# Punto1.net
KiCad netlist of a schematic drawn in Altium Designer
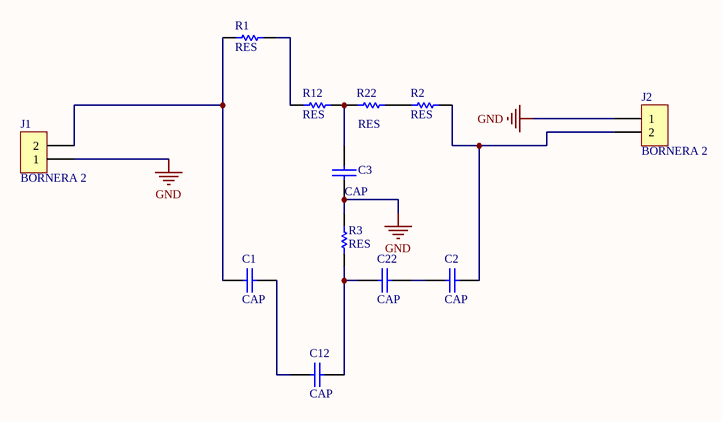
[diagram p0: Punto1.SchDoc]

(export (version "E")
  (design (tool "Eeschema 10.0.6"))
  (components
    (comp (ref "C1") (value "CAP") (footprint "CAP100") (libsource (lib "LIBEBAL") (part "CAP")))
    (comp (ref "C2") (value "CAP") (footprint "CAP100") (libsource (lib "LIBEBAL") (part "CAP")))
    (comp (ref "C3") (value "CAP") (footprint "CAP100") (libsource (lib "LIBEBAL") (part "CAP")))
    (comp (ref "C12") (value "CAP") (footprint "CAP100") (libsource (lib "LIBEBAL") (part "CAP")))
    (comp (ref "C22") (value "CAP") (footprint "CAP100") (libsource (lib "LIBEBAL") (part "CAP")))
    (comp (ref "J1") (value "BORNERA 2") (footprint "BORNERA2") (libsource (lib "") (part "BORNERA 2_1")))
    (comp (ref "J2")
      (value "BORNERA 2")
      (footprint "BORNERA2")
      (libsource (lib "LIBEBAL") (part "BORNERA 2"))
    )
    (comp (ref "R1") (value "RES") (footprint "RES400") (libsource (lib "LIBEBAL") (part "RES")))
    (comp (ref "R2") (value "RES") (footprint "RES400") (libsource (lib "LIBEBAL") (part "RES")))
    (comp (ref "R3") (value "RES") (footprint "RES400") (libsource (lib "LIBEBAL") (part "RES")))
    (comp (ref "R12") (value "RES") (footprint "RES400") (libsource (lib "LIBEBAL") (part "RES")))
    (comp (ref "R22") (value "RES") (footprint "RES400") (libsource (lib "LIBEBAL") (part "RES")))
  )
  (nets
    (net (code "1") (name "GND") (class "Default")
      (node (ref "C3") (pin "1") (pinfunction "1_1") (pintype "passive"))
      (node (ref "J1") (pin "1") (pinfunction "1_1") (pintype "passive"))
      (node (ref "J2") (pin "1") (pinfunction "1_1") (pintype "passive"))
      (node (ref "R3") (pin "2") (pinfunction "2_2") (pintype "passive"))
    )
    (net (code "2") (name "Net-(C1-Pad1)") (class "Default")
      (node (ref "C1") (pin "1") (pinfunction "1_1") (pintype "passive"))
      (node (ref "J1") (pin "2") (pinfunction "2_2") (pintype "passive"))
      (node (ref "R1") (pin "1") (pinfunction "1_1") (pintype "passive"))
    )
    (net (code "3") (name "Net-(C1-Pad2)") (class "Default")
      (node (ref "C1") (pin "2") (pinfunction "2_2") (pintype "passive"))
      (node (ref "C12") (pin "1") (pinfunction "1_1") (pintype "passive"))
    )
    (net (code "4") (name "Net-(C2-Pad1)") (class "Default")
      (node (ref "C2") (pin "1") (pinfunction "1_1") (pintype "passive"))
      (node (ref "C22") (pin "2") (pinfunction "2_2") (pintype "passive"))
    )
    (net (code "5") (name "Net-(C2-Pad2)") (class "Default")
      (node (ref "C2") (pin "2") (pinfunction "2_2") (pintype "passive"))
      (node (ref "J2") (pin "2") (pinfunction "2_2") (pintype "passive"))
      (node (ref "R2") (pin "2") (pinfunction "2_2") (pintype "passive"))
    )
    (net (code "6") (name "Net-(C3-Pad2)") (class "Default")
      (node (ref "C3") (pin "2") (pinfunction "2_2") (pintype "passive"))
      (node (ref "R12") (pin "2") (pinfunction "2_2") (pintype "passive"))
      (node (ref "R22") (pin "1") (pinfunction "1_1") (pintype "passive"))
    )
    (net (code "7") (name "Net-(C12-Pad2)") (class "Default")
      (node (ref "C12") (pin "2") (pinfunction "2_2") (pintype "passive"))
      (node (ref "C22") (pin "1") (pinfunction "1_1") (pintype "passive"))
      (node (ref "R3") (pin "1") (pinfunction "1_1") (pintype "passive"))
    )
    (net (code "8") (name "Net-(R1-Pad2)") (class "Default")
      (node (ref "R1") (pin "2") (pinfunction "2_2") (pintype "passive"))
      (node (ref "R12") (pin "1") (pinfunction "1_1") (pintype "passive"))
    )
    (net (code "9") (name "Net-(R2-Pad1)") (class "Default")
      (node (ref "R2") (pin "1") (pinfunction "1_1") (pintype "passive"))
      (node (ref "R22") (pin "2") (pinfunction "2_2") (pintype "passive"))
    )
  )
)
